# DMD_Card_Modules.net
KiCad netlist of a schematic drawn in Altium Designer
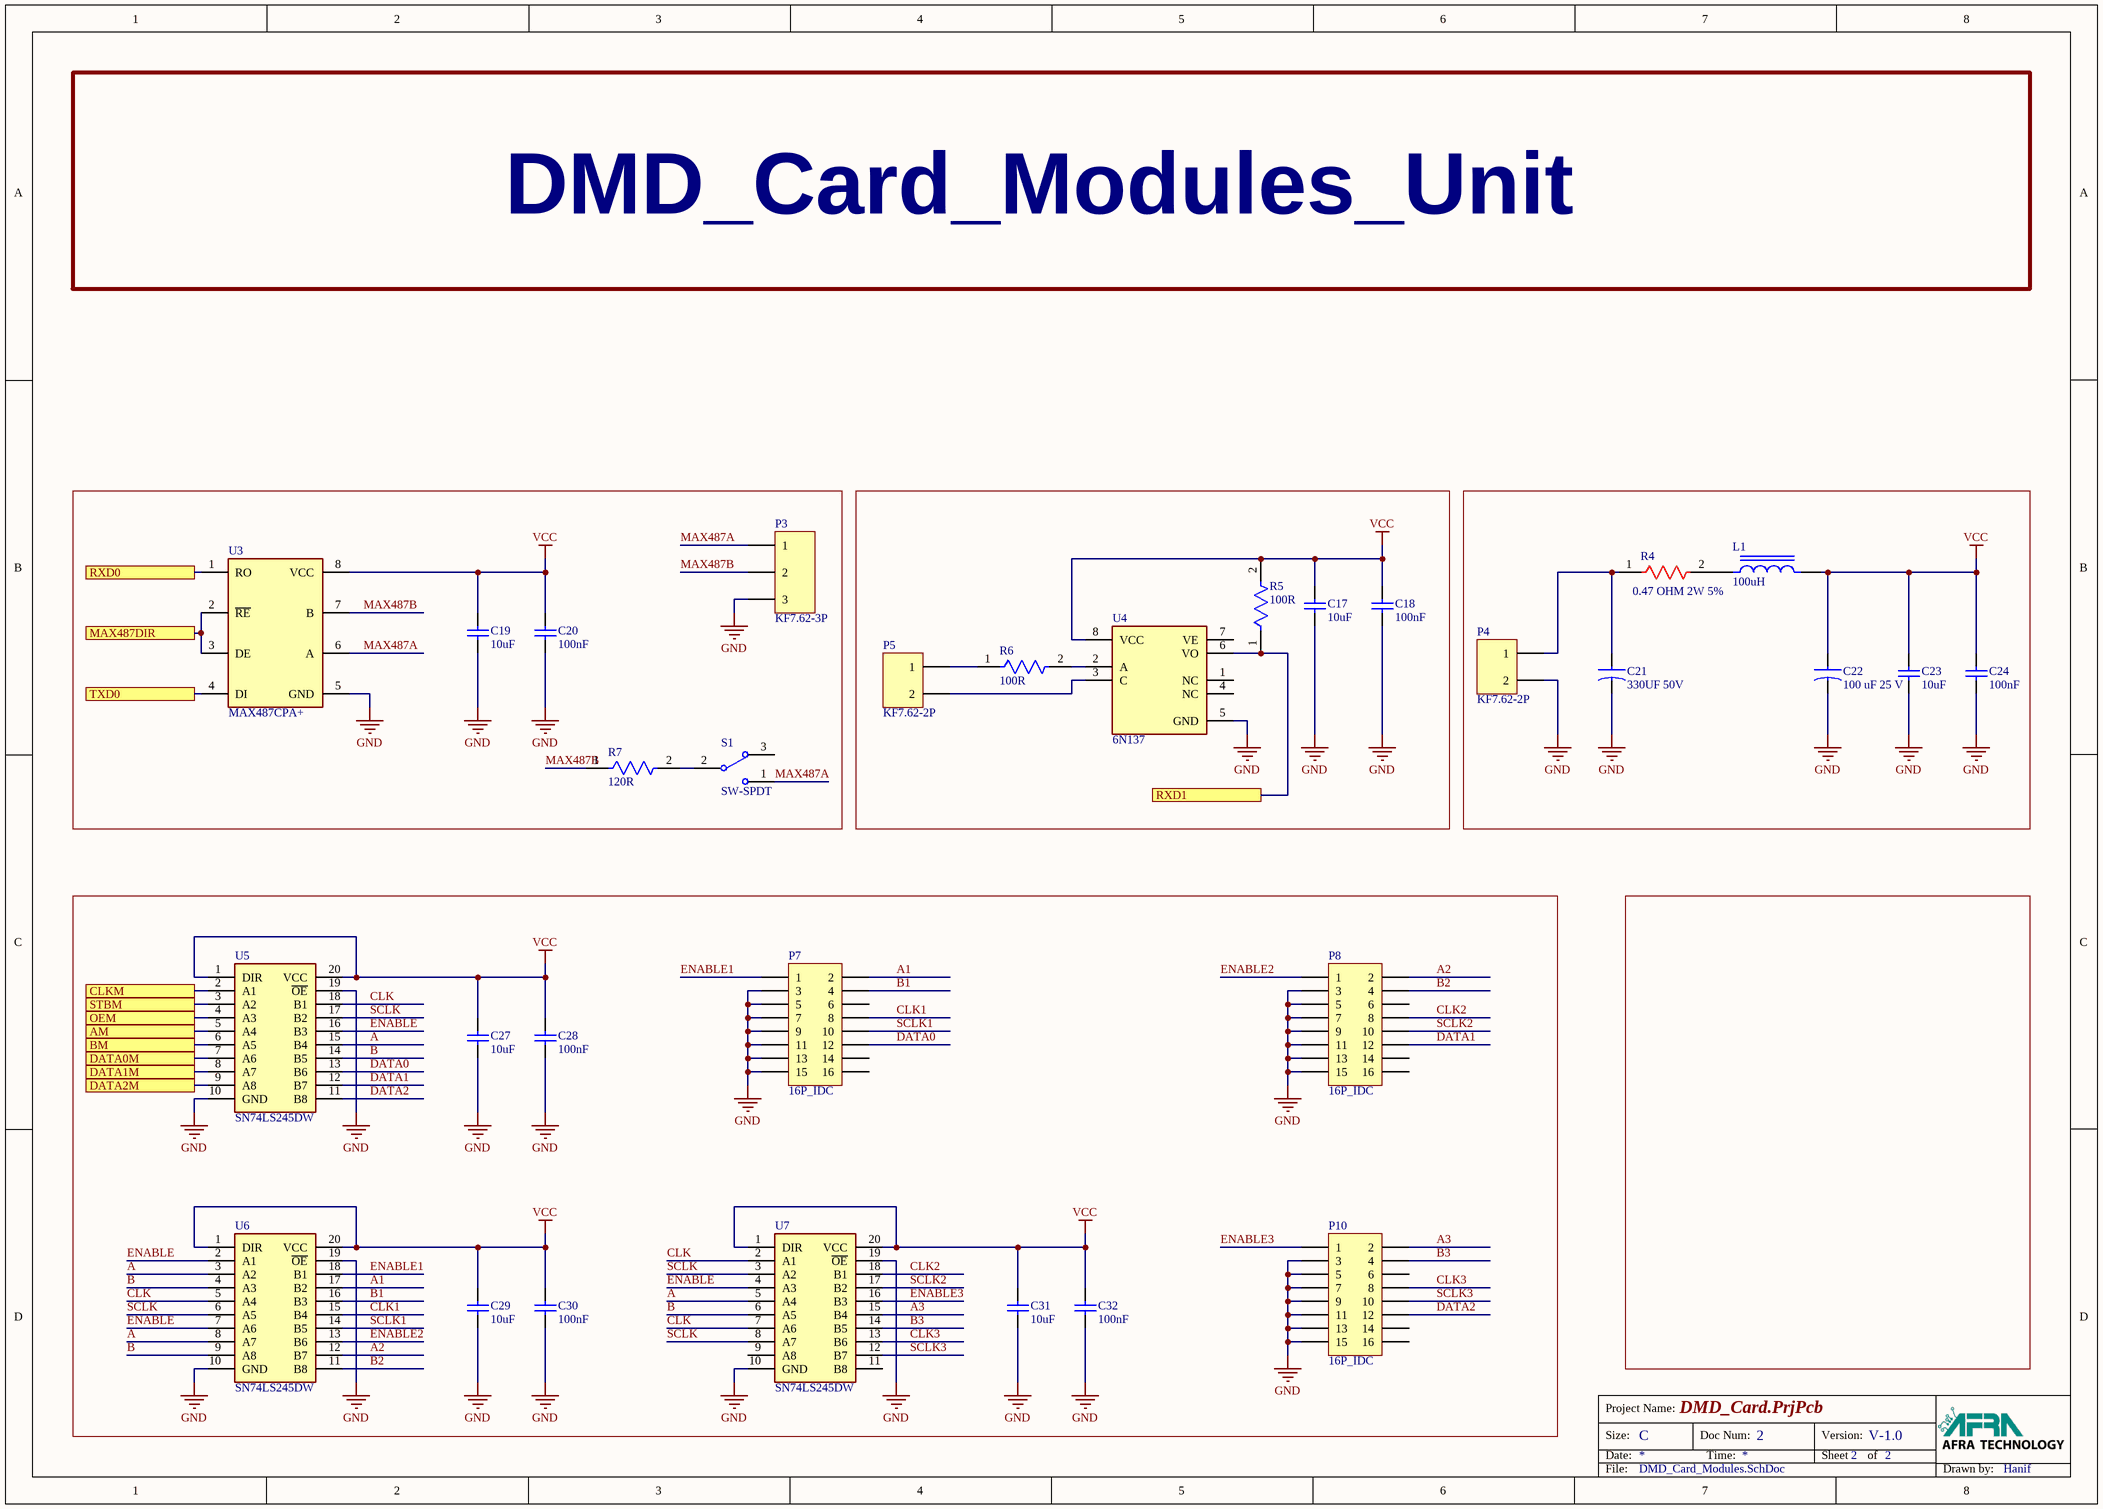
[diagram p0: DMD_Card_Modules.SchDoc]

(export (version "E")
  (design (tool "Eeschema 10.0.6"))
  (components
    (comp (ref "C17")
      (value "10uF")
      (footprint "Yageo_CC1206-1.25_IPC_A")
      (libsource (lib "DMD_Controller_Card") (part "CC1206KRX7R7BB334"))
    )
    (comp (ref "C18")
      (value "100nF")
      (footprint "Yageo_CC1206-1.25_IPC_A")
      (libsource (lib "DMD_Controller_Card") (part "CC1206KRX7R7BB104"))
    )
    (comp (ref "C19")
      (value "10uF")
      (footprint "Yageo_CC1206-1.25_IPC_A")
      (libsource (lib "DMD_Controller_Card") (part "CC1206KRX7R7BB334"))
    )
    (comp (ref "C20")
      (value "100nF")
      (footprint "Yageo_CC1206-1.25_IPC_A")
      (libsource (lib "DMD_Controller_Card") (part "CC1206KRX7R7BB104"))
    )
    (comp (ref "C21")
      (value "330UF 50V")
      (footprint "Multy_Radial_Capacitor")
      (description "Aluminum Electrolytic Capacitors Radial, Can - 10000 Hrs @ 105°C")
      (fields
        (field (name "MANUFACTURER") "Rubycon")
        (field (name "MANUFACTURER PART NUMBER") "50YXJ330M10X20")
      )
      (libsource (lib "DMD_Card") (part "330 uF 50 V Electrolytic Capacitors"))
    )
    (comp (ref "C22")
      (value "100 uF 25 V")
      (footprint "Multy_Radial_Capacitor")
      (description "RZ Series Radial 25 V 100 uF Ø 6.3 x 11 mm 105 °C Electrolytic Capacitor")
      (fields
        (field (name "MANUFACTURER") "Samwha")
        (field (name "MANUFACTURER PART NUMBER") "RZ1E107M6L011BB280")
      )
      (libsource (lib "DMD_Card") (part "100 uF 25 V Electrolytic Capacitor"))
    )
    (comp (ref "C23")
      (value "10uF")
      (footprint "Yageo_CC1206-1.25_IPC_A")
      (libsource (lib "DMD_Controller_Card") (part "CC1206KRX7R7BB334"))
    )
    (comp (ref "C24")
      (value "100nF")
      (footprint "Yageo_CC1206-1.25_IPC_A")
      (libsource (lib "DMD_Controller_Card") (part "CC1206KRX7R7BB104"))
    )
    (comp (ref "C27")
      (value "10uF")
      (footprint "Yageo_CC1206-1.25_IPC_A")
      (libsource (lib "DMD_Controller_Card") (part "CC1206KRX7R7BB334"))
    )
    (comp (ref "C28")
      (value "100nF")
      (footprint "Yageo_CC1206-1.25_IPC_A")
      (libsource (lib "DMD_Controller_Card") (part "CC1206KRX7R7BB104"))
    )
    (comp (ref "C29")
      (value "10uF")
      (footprint "Yageo_CC1206-1.25_IPC_A")
      (libsource (lib "DMD_Controller_Card") (part "CC1206KRX7R7BB334"))
    )
    (comp (ref "C30")
      (value "100nF")
      (footprint "Yageo_CC1206-1.25_IPC_A")
      (libsource (lib "DMD_Controller_Card") (part "CC1206KRX7R7BB104"))
    )
    (comp (ref "C31")
      (value "10uF")
      (footprint "Yageo_CC1206-1.25_IPC_A")
      (libsource (lib "DMD_Controller_Card") (part "CC1206KRX7R7BB334"))
    )
    (comp (ref "C32")
      (value "100nF")
      (footprint "Yageo_CC1206-1.25_IPC_A")
      (libsource (lib "DMD_Controller_Card") (part "CC1206KRX7R7BB104"))
    )
    (comp (ref "L1")
      (value "100uH")
      (footprint "Radia_03")
      (description "FIXED IND 100UH 320MA 600 MOHM")
      (fields
        (field (name "MANUFACTURER") "Bourns")
        (field (name "MANUFACTURER PART NUMBER") "RLB0812-101KL")
      )
      (libsource (lib "DMD_Card") (part "RLB0812-101KL"))
    )
    (comp (ref "P3")
      (value "KF7.62-3P")
      (footprint "KF7.62-3P Barrier Terminal Block")
      (libsource (lib "DMD_Card") (part "KF7.62-3P Barrier Terminal Block"))
    )
    (comp (ref "P4")
      (value "KF7.62-2P")
      (footprint "KF7.62-2P Barrier Terminal Block")
      (libsource (lib "DMD_Card") (part "KF7.62-2P Barrier Terminal Block"))
    )
    (comp (ref "P5")
      (value "KF7.62-2P")
      (footprint "KF7.62-2P Barrier Terminal Block")
      (libsource (lib "DMD_Card") (part "KF7.62-2P Barrier Terminal Block"))
    )
    (comp (ref "P7")
      (value "16P_IDC")
      (footprint "16Pin_IDC_Connector")
      (description "Headers & Wire Housings 16P STRAIGHT")
      (fields
        (field (name "MANUFACTURER") "Adam Equipment")
        (field (name "MANUFACTURER PART NUMBER") "BHR-16-VUA")
      )
      (libsource (lib "DMD_Card") (part "BHR-16-VUA"))
    )
    (comp (ref "P8")
      (value "16P_IDC")
      (footprint "16Pin_IDC_Connector")
      (description "Headers & Wire Housings 16P STRAIGHT")
      (fields
        (field (name "MANUFACTURER") "Adam Equipment")
        (field (name "MANUFACTURER PART NUMBER") "BHR-16-VUA")
      )
      (libsource (lib "DMD_Card") (part "BHR-16-VUA"))
    )
    (comp (ref "P10")
      (value "16P_IDC")
      (footprint "16Pin_IDC_Connector")
      (description "Headers & Wire Housings 16P STRAIGHT")
      (fields
        (field (name "MANUFACTURER") "Adam Equipment")
        (field (name "MANUFACTURER PART NUMBER") "BHR-16-VUA")
      )
      (libsource (lib "DMD_Card") (part "BHR-16-VUA"))
    )
    (comp (ref "R4")
      (value "0.47 OHM 2W 5%")
      (footprint "Axial 0.6")
      (description "RESISTOR 2 WATT METAL OXIDE FILM FLAMEPROOF 0.47 OHM 5% AXIAL LEAD")
      (fields
        (field (name "MANUFACTURER") "NTE Electronics")
        (field (name "MANUFACTURER PART NUMBER") "2WD47")
      )
      (libsource (lib "DMD_Card") (part "2WD47"))
    )
    (comp (ref "R5")
      (value "100R")
      (footprint "Yageo_RT1206_IPC_A")
      (libsource (lib "DMD_Controller_Card") (part "RT1206BRD07100RL"))
    )
    (comp (ref "R6")
      (value "100R")
      (footprint "Yageo_RT1206_IPC_A")
      (libsource (lib "DMD_Controller_Card") (part "RT1206BRD07100RL"))
    )
    (comp (ref "R7")
      (value "120R")
      (footprint "AXIAL 0.4")
      (description "RES 120 OHM 1/4W 0.1% AXIAL")
      (fields
        (field (name "MANUFACTURER") "Yageo")
        (field (name "MANUFACTURER PART NUMBER") "MFP-25BRD52-120R")
      )
      (libsource (lib "DMD_Card") (part "120R 1/4W"))
    )
    (comp (ref "S1")
      (value "SW-SPDT")
      (footprint "Toggle Switch_SPDT")
      (description "SPDT Subminiature Toggle Switch, Right Angle Mounting, Vertical Actuation")
      (fields (field (name "PUBLISHER") "Altium Limited"))
      (libsource (lib "Miscellaneous Devices") (part "SW-SPDT"))
    )
    (comp (ref "U3")
      (value "MAX487CPA+")
      (footprint "DIP_08")
      (description "Interface IC RS422/485 DIL-8, MAX487ECPA+, Maxim")
      (fields (field (name "MANUFACTURER") "Maxim") (field (name "MANUFACTURER PART NUMBER") "MAX487ECPA+"))
      (libsource (lib "DMD_Controller_Card") (part "MAX487ECPA+"))
    )
    (comp (ref "U4")
      (value "IC_Vishay_6N137_eec")
      (footprint "DIP_08")
      (description "IC OPTOISO 5.3KV 1CH OPN DRAIN 8DIP")
      (fields
        (field (name "MANUFACTURER") "Vishay")
        (field (name "MOUSER PART NUMBER") "782-6N137")
        (field (name "PART NUMBER") "6N137")
      )
      (libsource (lib "DMD_Controller_Card") (part "IC_Vishay_6N137_eec"))
    )
    (comp (ref "U5")
      (value "SN74LS245DW")
      (footprint "SOIC127P1030X265-20N")
      (description "Integrated Circuit")
      (fields (field (name "MOUSER PART NUMBER") "595-SN74LS245DW"))
      (libsource (lib "DMD_Controller_Card") (part "SN74LS245DW"))
    )
    (comp (ref "U6")
      (value "SN74LS245DW")
      (footprint "SOIC127P1030X265-20N")
      (description "Integrated Circuit")
      (fields (field (name "MOUSER PART NUMBER") "595-SN74LS245DW"))
      (libsource (lib "DMD_Controller_Card") (part "SN74LS245DW"))
    )
    (comp (ref "U7")
      (value "SN74LS245DW")
      (footprint "SOIC127P1030X265-20N")
      (description "Integrated Circuit")
      (fields (field (name "MOUSER PART NUMBER") "595-SN74LS245DW"))
      (libsource (lib "DMD_Controller_Card") (part "SN74LS245DW"))
    )
  )
  (nets
    (net (code "1") (name "/A") (class "Default")
      (node (ref "U5") (pin "15") (pinfunction "B4_15") (pintype "passive"))
      (node (ref "U6") (pin "3") (pinfunction "A2_3") (pintype "passive"))
      (node (ref "U6") (pin "8") (pinfunction "A7_8") (pintype "passive"))
      (node (ref "U7") (pin "5") (pinfunction "A4_5") (pintype "passive"))
    )
    (net (code "2") (name "/A1") (class "Default")
      (node (ref "P7") (pin "2") (pinfunction "2_2") (pintype "passive"))
      (node (ref "U6") (pin "17") (pinfunction "B2_17") (pintype "passive"))
    )
    (net (code "3") (name "/A2") (class "Default")
      (node (ref "P8") (pin "2") (pinfunction "2_2") (pintype "passive"))
      (node (ref "U6") (pin "12") (pinfunction "B7_12") (pintype "passive"))
    )
    (net (code "4") (name "/A3") (class "Default")
      (node (ref "P10") (pin "2") (pinfunction "2_2") (pintype "passive"))
      (node (ref "U7") (pin "15") (pinfunction "B4_15") (pintype "passive"))
    )
    (net (code "5") (name "/AM") (class "Default")
      (node (ref "U5") (pin "5") (pinfunction "A4_5") (pintype "passive"))
    )
    (net (code "6") (name "/B") (class "Default")
      (node (ref "U5") (pin "14") (pinfunction "B5_14") (pintype "passive"))
      (node (ref "U6") (pin "4") (pinfunction "A3_4") (pintype "passive"))
      (node (ref "U6") (pin "9") (pinfunction "A8_9") (pintype "passive"))
      (node (ref "U7") (pin "6") (pinfunction "A5_6") (pintype "passive"))
    )
    (net (code "7") (name "/B1") (class "Default")
      (node (ref "P7") (pin "4") (pinfunction "4_4") (pintype "passive"))
      (node (ref "U6") (pin "16") (pinfunction "B3_16") (pintype "passive"))
    )
    (net (code "8") (name "/B2") (class "Default")
      (node (ref "P8") (pin "4") (pinfunction "4_4") (pintype "passive"))
      (node (ref "U6") (pin "11") (pinfunction "B8_11") (pintype "passive"))
    )
    (net (code "9") (name "/B3") (class "Default")
      (node (ref "P10") (pin "4") (pinfunction "4_4") (pintype "passive"))
      (node (ref "U7") (pin "14") (pinfunction "B5_14") (pintype "passive"))
    )
    (net (code "10") (name "/BM") (class "Default")
      (node (ref "U5") (pin "6") (pinfunction "A5_6") (pintype "passive"))
    )
    (net (code "11") (name "/CLK") (class "Default")
      (node (ref "U5") (pin "18") (pinfunction "B1_18") (pintype "passive"))
      (node (ref "U6") (pin "5") (pinfunction "A4_5") (pintype "passive"))
      (node (ref "U7") (pin "2") (pinfunction "A1_2") (pintype "passive"))
      (node (ref "U7") (pin "7") (pinfunction "A6_7") (pintype "passive"))
    )
    (net (code "12") (name "/CLK1") (class "Default")
      (node (ref "P7") (pin "8") (pinfunction "8_8") (pintype "passive"))
      (node (ref "U6") (pin "15") (pinfunction "B4_15") (pintype "passive"))
    )
    (net (code "13") (name "/CLK2") (class "Default")
      (node (ref "P8") (pin "8") (pinfunction "8_8") (pintype "passive"))
      (node (ref "U7") (pin "18") (pinfunction "B1_18") (pintype "passive"))
    )
    (net (code "14") (name "/CLK3") (class "Default")
      (node (ref "P10") (pin "8") (pinfunction "8_8") (pintype "passive"))
      (node (ref "U7") (pin "13") (pinfunction "B6_13") (pintype "passive"))
    )
    (net (code "15") (name "/CLKM") (class "Default")
      (node (ref "U5") (pin "2") (pinfunction "A1_2") (pintype "passive"))
    )
    (net (code "16") (name "/DATA0") (class "Default")
      (node (ref "P7") (pin "12") (pinfunction "12_12") (pintype "passive"))
      (node (ref "U5") (pin "13") (pinfunction "B6_13") (pintype "passive"))
    )
    (net (code "17") (name "/DATA0M") (class "Default")
      (node (ref "U5") (pin "7") (pinfunction "A6_7") (pintype "passive"))
    )
    (net (code "18") (name "/DATA1") (class "Default")
      (node (ref "P8") (pin "12") (pinfunction "12_12") (pintype "passive"))
      (node (ref "U5") (pin "12") (pinfunction "B7_12") (pintype "passive"))
    )
    (net (code "19") (name "/DATA1M") (class "Default")
      (node (ref "U5") (pin "8") (pinfunction "A7_8") (pintype "passive"))
    )
    (net (code "20") (name "/DATA2") (class "Default")
      (node (ref "P10") (pin "12") (pinfunction "12_12") (pintype "passive"))
      (node (ref "U5") (pin "11") (pinfunction "B8_11") (pintype "passive"))
    )
    (net (code "21") (name "/DATA2M") (class "Default")
      (node (ref "U5") (pin "9") (pinfunction "A8_9") (pintype "passive"))
    )
    (net (code "22") (name "/ENABLE") (class "Default")
      (node (ref "U5") (pin "16") (pinfunction "B3_16") (pintype "passive"))
      (node (ref "U6") (pin "2") (pinfunction "A1_2") (pintype "passive"))
      (node (ref "U6") (pin "7") (pinfunction "A6_7") (pintype "passive"))
      (node (ref "U7") (pin "4") (pinfunction "A3_4") (pintype "passive"))
    )
    (net (code "23") (name "/ENABLE1") (class "Default")
      (node (ref "P7") (pin "1") (pinfunction "1_1") (pintype "passive"))
      (node (ref "U6") (pin "18") (pinfunction "B1_18") (pintype "passive"))
    )
    (net (code "24") (name "/ENABLE2") (class "Default")
      (node (ref "P8") (pin "1") (pinfunction "1_1") (pintype "passive"))
      (node (ref "U6") (pin "13") (pinfunction "B6_13") (pintype "passive"))
    )
    (net (code "25") (name "/ENABLE3") (class "Default")
      (node (ref "P10") (pin "1") (pinfunction "1_1") (pintype "passive"))
      (node (ref "U7") (pin "16") (pinfunction "B3_16") (pintype "passive"))
    )
    (net (code "26") (name "/MAX487A") (class "Default")
      (node (ref "P3") (pin "1") (pinfunction "1_1") (pintype "passive"))
      (node (ref "S1") (pin "1") (pinfunction "1_1") (pintype "passive"))
      (node (ref "U3") (pin "6") (pinfunction "A_6") (pintype "passive"))
    )
    (net (code "27") (name "/MAX487B") (class "Default")
      (node (ref "P3") (pin "2") (pinfunction "2_2") (pintype "passive"))
      (node (ref "R7") (pin "1") (pinfunction "1_1") (pintype "passive"))
      (node (ref "U3") (pin "7") (pinfunction "B_7") (pintype "passive"))
    )
    (net (code "28") (name "/MAX487DIR") (class "Default")
      (node (ref "U3") (pin "2") (pinfunction "~{RE}_2") (pintype "passive"))
      (node (ref "U3") (pin "3") (pinfunction "DE_3") (pintype "passive"))
    )
    (net (code "29") (name "/OEM") (class "Default")
      (node (ref "U5") (pin "4") (pinfunction "A3_4") (pintype "passive"))
    )
    (net (code "30") (name "/RXD0") (class "Default")
      (node (ref "U3") (pin "1") (pinfunction "RO_1") (pintype "passive"))
    )
    (net (code "31") (name "/RXD1") (class "Default")
      (node (ref "R5") (pin "1") (pinfunction "1_1") (pintype "passive"))
      (node (ref "U4") (pin "6") (pinfunction "VO_6") (pintype "passive"))
    )
    (net (code "32") (name "/SCLK") (class "Default")
      (node (ref "U5") (pin "17") (pinfunction "B2_17") (pintype "passive"))
      (node (ref "U6") (pin "6") (pinfunction "A5_6") (pintype "passive"))
      (node (ref "U7") (pin "3") (pinfunction "A2_3") (pintype "passive"))
      (node (ref "U7") (pin "8") (pinfunction "A7_8") (pintype "passive"))
    )
    (net (code "33") (name "/SCLK1") (class "Default")
      (node (ref "P7") (pin "10") (pinfunction "10_10") (pintype "passive"))
      (node (ref "U6") (pin "14") (pinfunction "B5_14") (pintype "passive"))
    )
    (net (code "34") (name "/SCLK2") (class "Default")
      (node (ref "P8") (pin "10") (pinfunction "10_10") (pintype "passive"))
      (node (ref "U7") (pin "17") (pinfunction "B2_17") (pintype "passive"))
    )
    (net (code "35") (name "/SCLK3") (class "Default")
      (node (ref "P10") (pin "10") (pinfunction "10_10") (pintype "passive"))
      (node (ref "U7") (pin "12") (pinfunction "B7_12") (pintype "passive"))
    )
    (net (code "36") (name "/STBM") (class "Default")
      (node (ref "U5") (pin "3") (pinfunction "A2_3") (pintype "passive"))
    )
    (net (code "37") (name "/TXD0") (class "Default")
      (node (ref "U3") (pin "4") (pinfunction "DI_4") (pintype "passive"))
    )
    (net (code "38") (name "GND") (class "Default")
      (node (ref "C17") (pin "1") (pinfunction "1_1") (pintype "passive"))
      (node (ref "C18") (pin "1") (pinfunction "1_1") (pintype "passive"))
      (node (ref "C19") (pin "1") (pinfunction "1_1") (pintype "passive"))
      (node (ref "C20") (pin "1") (pinfunction "1_1") (pintype "passive"))
      (node (ref "C21") (pin "2") (pinfunction "2_2") (pintype "passive"))
      (node (ref "C22") (pin "2") (pinfunction "2_2") (pintype "passive"))
      (node (ref "C23") (pin "1") (pinfunction "1_1") (pintype "passive"))
      (node (ref "C24") (pin "1") (pinfunction "1_1") (pintype "passive"))
      (node (ref "C27") (pin "1") (pinfunction "1_1") (pintype "passive"))
      (node (ref "C28") (pin "1") (pinfunction "1_1") (pintype "passive"))
      (node (ref "C29") (pin "1") (pinfunction "1_1") (pintype "passive"))
      (node (ref "C30") (pin "1") (pinfunction "1_1") (pintype "passive"))
      (node (ref "C31") (pin "1") (pinfunction "1_1") (pintype "passive"))
      (node (ref "C32") (pin "1") (pinfunction "1_1") (pintype "passive"))
      (node (ref "P10") (pin "11") (pinfunction "11_11") (pintype "passive"))
      (node (ref "P10") (pin "13") (pinfunction "13_13") (pintype "passive"))
      (node (ref "P10") (pin "15") (pinfunction "15_15") (pintype "passive"))
      (node (ref "P10") (pin "3") (pinfunction "3_3") (pintype "passive"))
      (node (ref "P10") (pin "5") (pinfunction "5_5") (pintype "passive"))
      (node (ref "P10") (pin "7") (pinfunction "7_7") (pintype "passive"))
      (node (ref "P10") (pin "9") (pinfunction "9_9") (pintype "passive"))
      (node (ref "P3") (pin "3") (pinfunction "3_3") (pintype "passive"))
      (node (ref "P4") (pin "2") (pinfunction "2_2") (pintype "passive"))
      (node (ref "P7") (pin "11") (pinfunction "11_11") (pintype "passive"))
      (node (ref "P7") (pin "13") (pinfunction "13_13") (pintype "passive"))
      (node (ref "P7") (pin "15") (pinfunction "15_15") (pintype "passive"))
      (node (ref "P7") (pin "3") (pinfunction "3_3") (pintype "passive"))
      (node (ref "P7") (pin "5") (pinfunction "5_5") (pintype "passive"))
      (node (ref "P7") (pin "7") (pinfunction "7_7") (pintype "passive"))
      (node (ref "P7") (pin "9") (pinfunction "9_9") (pintype "passive"))
      (node (ref "P8") (pin "11") (pinfunction "11_11") (pintype "passive"))
      (node (ref "P8") (pin "13") (pinfunction "13_13") (pintype "passive"))
      (node (ref "P8") (pin "15") (pinfunction "15_15") (pintype "passive"))
      (node (ref "P8") (pin "3") (pinfunction "3_3") (pintype "passive"))
      (node (ref "P8") (pin "5") (pinfunction "5_5") (pintype "passive"))
      (node (ref "P8") (pin "7") (pinfunction "7_7") (pintype "passive"))
      (node (ref "P8") (pin "9") (pinfunction "9_9") (pintype "passive"))
      (node (ref "U3") (pin "5") (pinfunction "GND_5") (pintype "passive"))
      (node (ref "U4") (pin "5") (pinfunction "GND_5") (pintype "passive"))
      (node (ref "U5") (pin "10") (pinfunction "GND_10") (pintype "passive"))
      (node (ref "U5") (pin "19") (pinfunction "~{OE}_19") (pintype "passive"))
      (node (ref "U6") (pin "10") (pinfunction "GND_10") (pintype "passive"))
      (node (ref "U6") (pin "19") (pinfunction "~{OE}_19") (pintype "passive"))
      (node (ref "U7") (pin "10") (pinfunction "GND_10") (pintype "passive"))
      (node (ref "U7") (pin "19") (pinfunction "~{OE}_19") (pintype "passive"))
    )
    (net (code "39") (name "Net-(C21-Pad1)") (class "Default")
      (node (ref "C21") (pin "1") (pinfunction "1_1") (pintype "passive"))
      (node (ref "P4") (pin "1") (pinfunction "1_1") (pintype "passive"))
      (node (ref "R4") (pin "1") (pinfunction "1_1") (pintype "passive"))
    )
    (net (code "40") (name "Net-(L1-Pad1)") (class "Default")
      (node (ref "L1") (pin "1") (pinfunction "1_1") (pintype "passive"))
      (node (ref "R4") (pin "2") (pinfunction "2_2") (pintype "passive"))
    )
    (net (code "41") (name "Net-(P5-Pad1)") (class "Default")
      (node (ref "P5") (pin "1") (pinfunction "1_1") (pintype "passive"))
      (node (ref "R6") (pin "1") (pinfunction "1_1") (pintype "passive"))
    )
    (net (code "42") (name "Net-(R7-Pad2)") (class "Default")
      (node (ref "R7") (pin "2") (pinfunction "2_2") (pintype "passive"))
      (node (ref "S1") (pin "2") (pinfunction "2_2") (pintype "passive"))
    )
    (net (code "43") (name "Net-(U4-A)") (class "Default")
      (node (ref "R6") (pin "2") (pinfunction "2_2") (pintype "passive"))
      (node (ref "U4") (pin "2") (pinfunction "A_2") (pintype "passive"))
    )
    (net (code "44") (name "Net-(U4-C)") (class "Default")
      (node (ref "P5") (pin "2") (pinfunction "2_2") (pintype "passive"))
      (node (ref "U4") (pin "3") (pinfunction "C_3") (pintype "passive"))
    )
    (net (code "45") (name "VCC") (class "Default")
      (node (ref "C17") (pin "2") (pinfunction "2_2") (pintype "passive"))
      (node (ref "C18") (pin "2") (pinfunction "2_2") (pintype "passive"))
      (node (ref "C19") (pin "2") (pinfunction "2_2") (pintype "passive"))
      (node (ref "C20") (pin "2") (pinfunction "2_2") (pintype "passive"))
      (node (ref "C22") (pin "1") (pinfunction "1_1") (pintype "passive"))
      (node (ref "C23") (pin "2") (pinfunction "2_2") (pintype "passive"))
      (node (ref "C24") (pin "2") (pinfunction "2_2") (pintype "passive"))
      (node (ref "C27") (pin "2") (pinfunction "2_2") (pintype "passive"))
      (node (ref "C28") (pin "2") (pinfunction "2_2") (pintype "passive"))
      (node (ref "C29") (pin "2") (pinfunction "2_2") (pintype "passive"))
      (node (ref "C30") (pin "2") (pinfunction "2_2") (pintype "passive"))
      (node (ref "C31") (pin "2") (pinfunction "2_2") (pintype "passive"))
      (node (ref "C32") (pin "2") (pinfunction "2_2") (pintype "passive"))
      (node (ref "L1") (pin "2") (pinfunction "2_2") (pintype "passive"))
      (node (ref "R5") (pin "2") (pinfunction "2_2") (pintype "passive"))
      (node (ref "U3") (pin "8") (pinfunction "VCC_8") (pintype "passive"))
      (node (ref "U4") (pin "8") (pinfunction "VCC_8") (pintype "passive"))
      (node (ref "U5") (pin "1") (pinfunction "DIR_1") (pintype "passive"))
      (node (ref "U5") (pin "20") (pinfunction "VCC_20") (pintype "passive"))
      (node (ref "U6") (pin "1") (pinfunction "DIR_1") (pintype "passive"))
      (node (ref "U6") (pin "20") (pinfunction "VCC_20") (pintype "passive"))
      (node (ref "U7") (pin "1") (pinfunction "DIR_1") (pintype "passive"))
      (node (ref "U7") (pin "20") (pinfunction "VCC_20") (pintype "passive"))
    )
    (net (code "46") (name "unconnected-(P7-Pad6)") (class "Default")
      (node (ref "P7") (pin "6") (pinfunction "6_6") (pintype "passive"))
    )
    (net (code "47") (name "unconnected-(P7-Pad14)") (class "Default")
      (node (ref "P7") (pin "14") (pinfunction "14_14") (pintype "passive"))
    )
    (net (code "48") (name "unconnected-(P7-Pad16)") (class "Default")
      (node (ref "P7") (pin "16") (pinfunction "16_16") (pintype "passive"))
    )
    (net (code "49") (name "unconnected-(P8-Pad6)") (class "Default")
      (node (ref "P8") (pin "6") (pinfunction "6_6") (pintype "passive"))
    )
    (net (code "50") (name "unconnected-(P8-Pad14)") (class "Default")
      (node (ref "P8") (pin "14") (pinfunction "14_14") (pintype "passive"))
    )
    (net (code "51") (name "unconnected-(P8-Pad16)") (class "Default")
      (node (ref "P8") (pin "16") (pinfunction "16_16") (pintype "passive"))
    )
    (net (code "52") (name "unconnected-(P10-Pad6)") (class "Default")
      (node (ref "P10") (pin "6") (pinfunction "6_6") (pintype "passive"))
    )
    (net (code "53") (name "unconnected-(P10-Pad14)") (class "Default")
      (node (ref "P10") (pin "14") (pinfunction "14_14") (pintype "passive"))
    )
    (net (code "54") (name "unconnected-(P10-Pad16)") (class "Default")
      (node (ref "P10") (pin "16") (pinfunction "16_16") (pintype "passive"))
    )
    (net (code "55") (name "unconnected-(S1-Pad3)") (class "Default")
      (node (ref "S1") (pin "3") (pinfunction "3_3") (pintype "passive"))
    )
    (net (code "56") (name "unconnected-(U4-NC-Pad1)") (class "Default")
      (node (ref "U4") (pin "1") (pinfunction "NC_1") (pintype "passive"))
    )
    (net (code "57") (name "unconnected-(U4-NC-Pad4)") (class "Default")
      (node (ref "U4") (pin "4") (pinfunction "NC_4") (pintype "passive"))
    )
    (net (code "58") (name "unconnected-(U4-VE-Pad7)") (class "Default")
      (node (ref "U4") (pin "7") (pinfunction "VE_7") (pintype "passive"))
    )
    (net (code "59") (name "unconnected-(U7-A8-Pad9)") (class "Default")
      (node (ref "U7") (pin "9") (pinfunction "A8_9") (pintype "passive"))
    )
    (net (code "60") (name "unconnected-(U7-B8-Pad11)") (class "Default")
      (node (ref "U7") (pin "11") (pinfunction "B8_11") (pintype "passive"))
    )
  )
)
